# SCH_PROJETO-AFC-_LAYOUT-ATUALIZADO-002__.net
KiCad netlist of a schematic drawn in EasyEDA
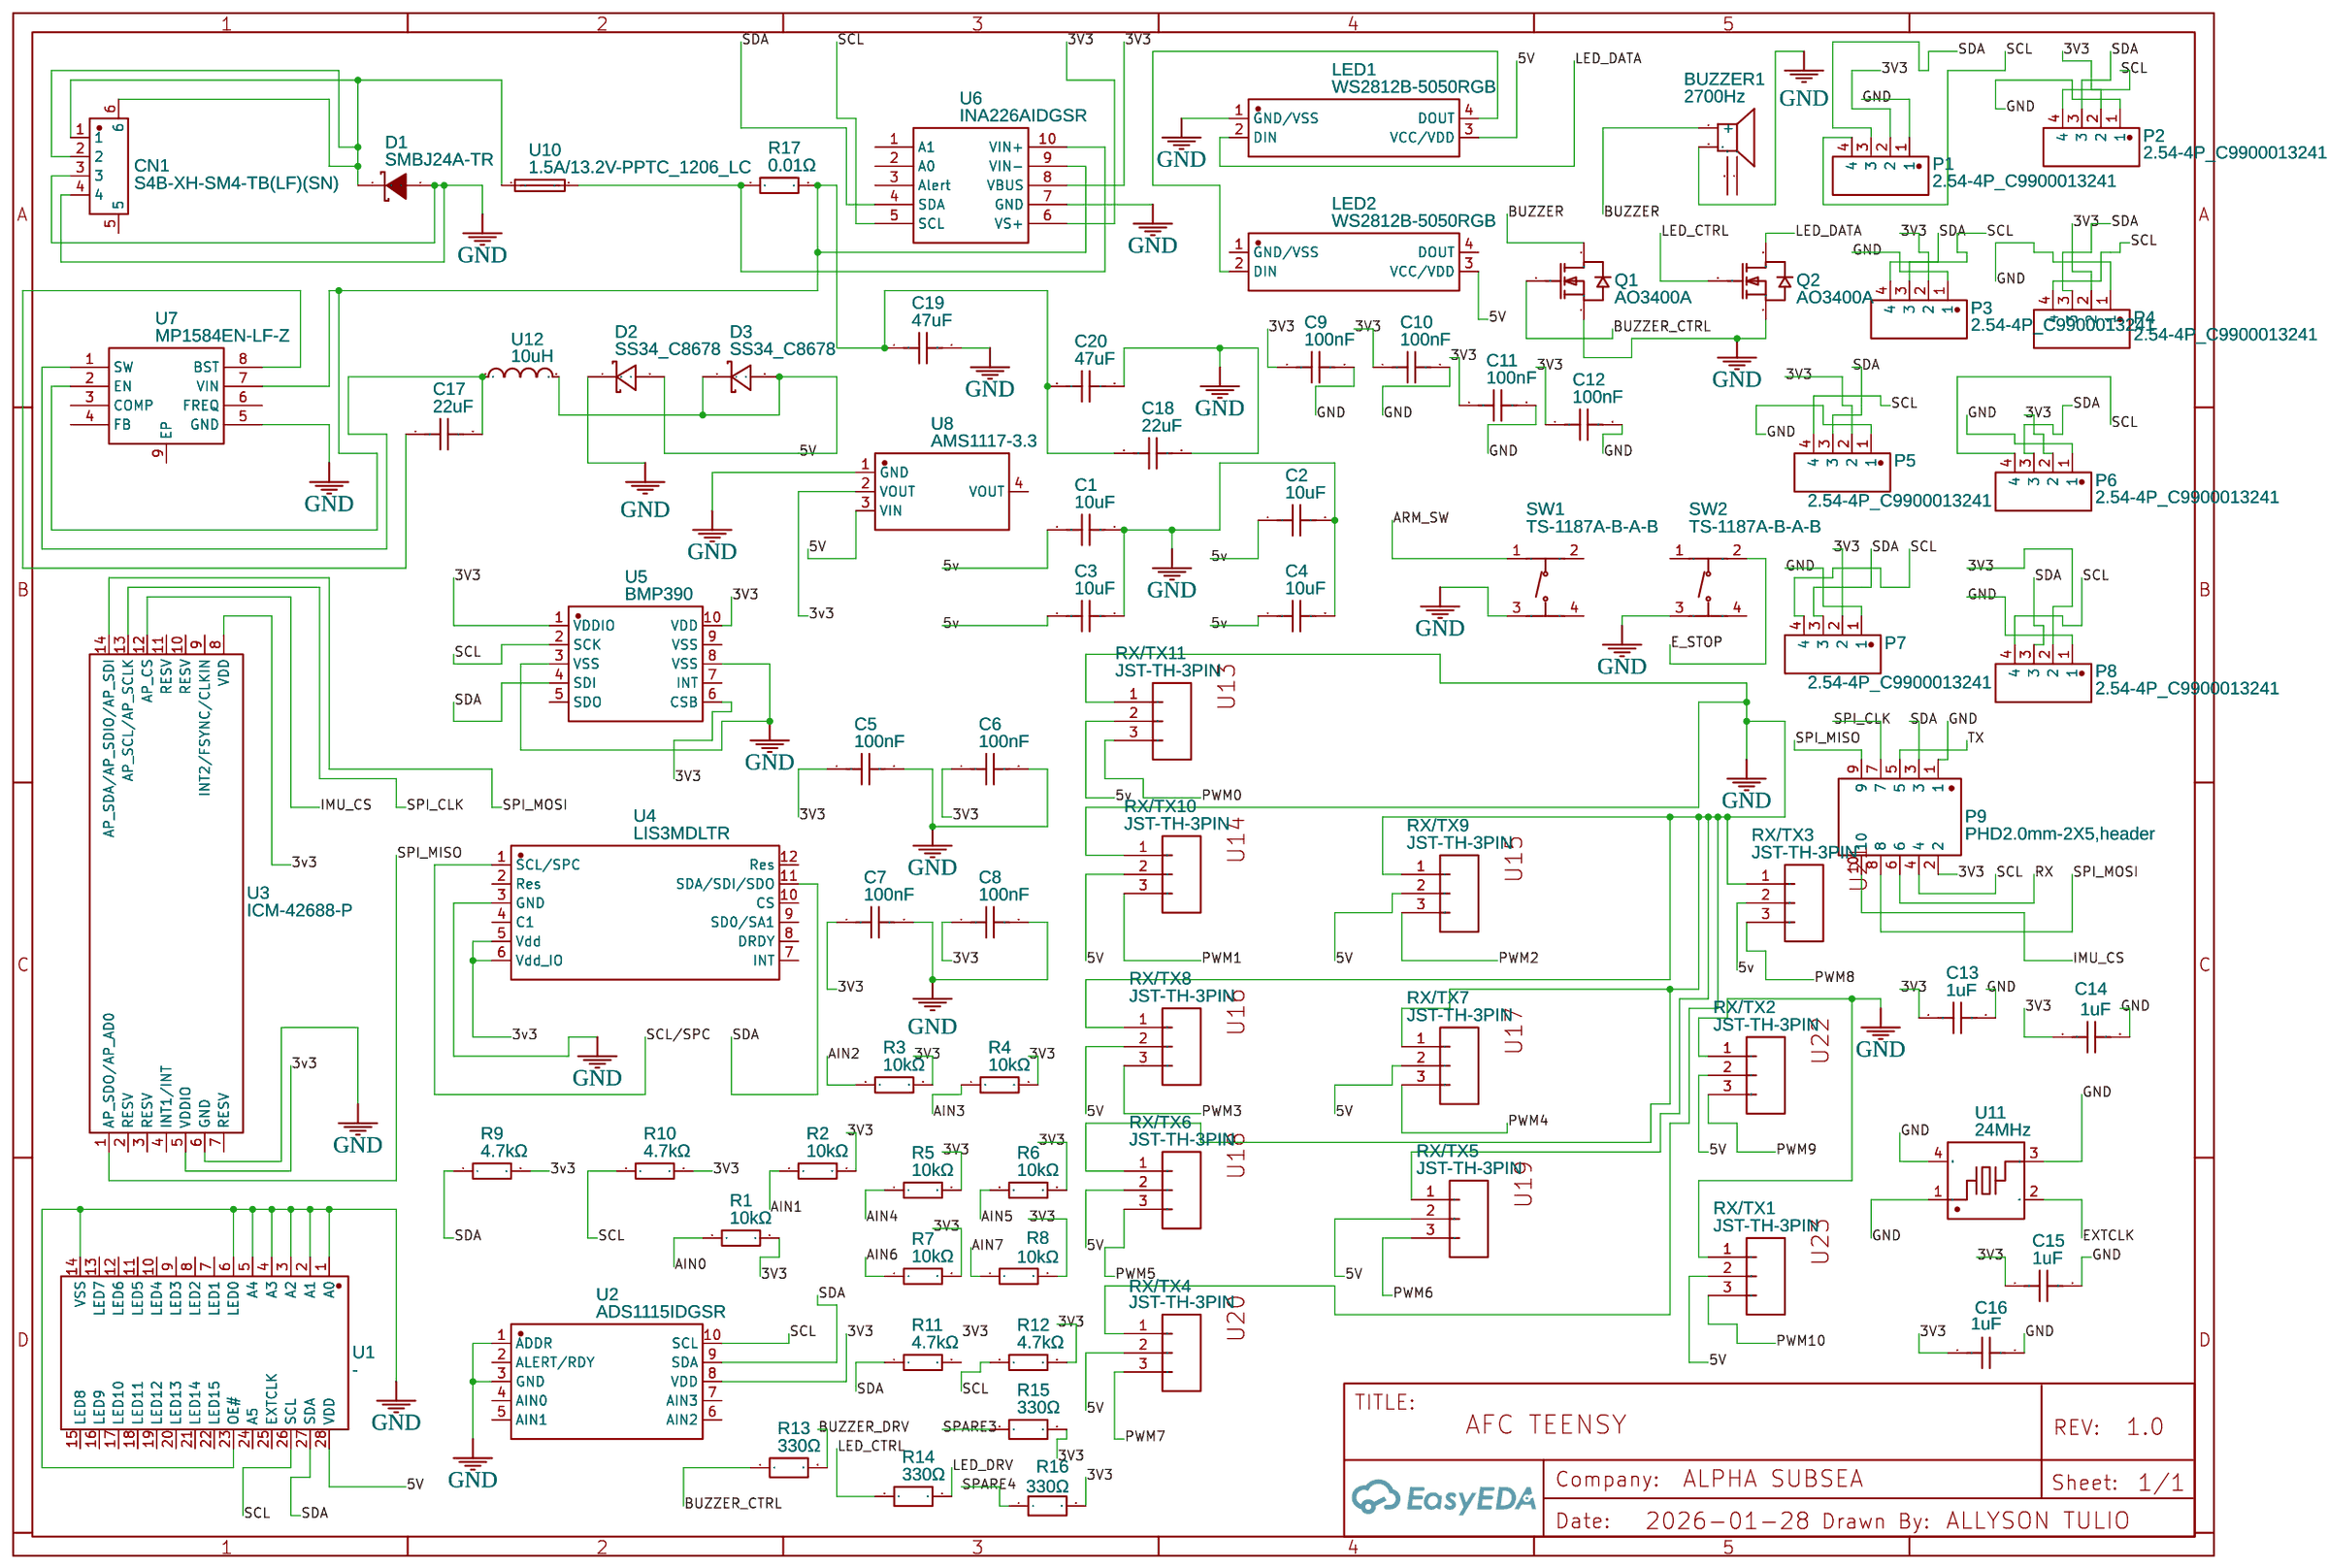
[diagram p0: schematic sheet]

(export (version "E")
  (design (tool "Eeschema 10.0.6"))
  (components
    (comp (ref "BUZZER1")
      (value "2700Hz")
      (fields (field (name "Manufacturer Part") "MLT-8530") (field (name "Manufacturer") "华能"))
      (libsource (lib "") (part "MLT-8530"))
    )
    (comp (ref "C1")
      (value "10uF")
      (fields
        (field (name "Manufacturer Part") "CL21A106KAYNNNE")
        (field (name "Manufacturer") "SAMSUNG(三星)")
      )
      (libsource (lib "") (part "CL21A106KAYNNNE"))
    )
    (comp (ref "C2")
      (value "10uF")
      (fields
        (field (name "Manufacturer Part") "CL21A106KAYNNNE")
        (field (name "Manufacturer") "SAMSUNG(三星)")
      )
      (libsource (lib "") (part "CL21A106KAYNNNE"))
    )
    (comp (ref "C3")
      (value "10uF")
      (fields
        (field (name "Manufacturer Part") "CL21A106KAYNNNE")
        (field (name "Manufacturer") "SAMSUNG(三星)")
      )
      (libsource (lib "") (part "CL21A106KAYNNNE"))
    )
    (comp (ref "C4")
      (value "10uF")
      (fields
        (field (name "Manufacturer Part") "CL21A106KAYNNNE")
        (field (name "Manufacturer") "SAMSUNG(三星)")
      )
      (libsource (lib "") (part "CL21A106KAYNNNE"))
    )
    (comp (ref "C5")
      (value "100nF")
      (fields
        (field (name "Manufacturer Part") "CL05B104KO5NNNC")
        (field (name "Manufacturer") "SAMSUNG(三星)")
      )
      (libsource (lib "") (part "CL05B104KO5NNNC"))
    )
    (comp (ref "C6")
      (value "100nF")
      (fields
        (field (name "Manufacturer Part") "CL05B104KO5NNNC")
        (field (name "Manufacturer") "SAMSUNG(三星)")
      )
      (libsource (lib "") (part "CL05B104KO5NNNC"))
    )
    (comp (ref "C7")
      (value "100nF")
      (fields
        (field (name "Manufacturer Part") "CL05B104KO5NNNC")
        (field (name "Manufacturer") "SAMSUNG(三星)")
      )
      (libsource (lib "") (part "CL05B104KO5NNNC"))
    )
    (comp (ref "C8")
      (value "100nF")
      (fields
        (field (name "Manufacturer Part") "CL05B104KO5NNNC")
        (field (name "Manufacturer") "SAMSUNG(三星)")
      )
      (libsource (lib "") (part "CL05B104KO5NNNC"))
    )
    (comp (ref "C9")
      (value "100nF")
      (fields
        (field (name "Manufacturer Part") "CL05B104KO5NNNC")
        (field (name "Manufacturer") "SAMSUNG(三星)")
      )
      (libsource (lib "") (part "CL05B104KO5NNNC"))
    )
    (comp (ref "C10")
      (value "100nF")
      (fields
        (field (name "Manufacturer Part") "CL05B104KO5NNNC")
        (field (name "Manufacturer") "SAMSUNG(三星)")
      )
      (libsource (lib "") (part "CL05B104KO5NNNC"))
    )
    (comp (ref "C11")
      (value "100nF")
      (fields
        (field (name "Manufacturer Part") "CL05B104KO5NNNC")
        (field (name "Manufacturer") "SAMSUNG(三星)")
      )
      (libsource (lib "") (part "CL05B104KO5NNNC"))
    )
    (comp (ref "C12")
      (value "100nF")
      (fields
        (field (name "Manufacturer Part") "CL05B104KO5NNNC")
        (field (name "Manufacturer") "SAMSUNG(三星)")
      )
      (libsource (lib "") (part "CL05B104KO5NNNC"))
    )
    (comp (ref "C13")
      (value "1uF")
      (fields
        (field (name "Manufacturer Part") "CL05A105KA5NQNC")
        (field (name "Manufacturer") "SAMSUNG(三星)")
      )
      (libsource (lib "") (part "CL05A105KA5NQNC"))
    )
    (comp (ref "C14")
      (value "1uF")
      (fields
        (field (name "Manufacturer Part") "CL05A105KA5NQNC")
        (field (name "Manufacturer") "SAMSUNG(三星)")
      )
      (libsource (lib "") (part "CL05A105KA5NQNC"))
    )
    (comp (ref "C15")
      (value "1uF")
      (fields
        (field (name "Manufacturer Part") "CL05A105KA5NQNC")
        (field (name "Manufacturer") "SAMSUNG(三星)")
      )
      (libsource (lib "") (part "CL05A105KA5NQNC"))
    )
    (comp (ref "C16")
      (value "1uF")
      (fields
        (field (name "Manufacturer Part") "CL05A105KA5NQNC")
        (field (name "Manufacturer") "SAMSUNG(三星)")
      )
      (libsource (lib "") (part "CL05A105KA5NQNC"))
    )
    (comp (ref "C17")
      (value "22uF")
      (fields
        (field (name "Manufacturer Part") "CL21A226MAQNNNE")
        (field (name "Manufacturer") "SAMSUNG(三星)")
      )
      (libsource (lib "") (part "CL21A226MAQNNNE"))
    )
    (comp (ref "C18")
      (value "22uF")
      (fields
        (field (name "Manufacturer Part") "CL21A226MAQNNNE")
        (field (name "Manufacturer") "SAMSUNG(三星)")
      )
      (libsource (lib "") (part "CL21A226MAQNNNE"))
    )
    (comp (ref "C19")
      (value "47uF")
      (fields
        (field (name "Manufacturer Part") "TCC1206X5R476M100HT")
        (field (name "Manufacturer") "CCTC(三环)")
      )
      (libsource (lib "") (part "TCC1206X5R476M100HT"))
    )
    (comp (ref "C20")
      (value "47uF")
      (fields
        (field (name "Manufacturer Part") "TCC1206X5R476M100HT")
        (field (name "Manufacturer") "CCTC(三环)")
      )
      (libsource (lib "") (part "TCC1206X5R476M100HT"))
    )
    (comp (ref "CN1")
      (value "S4B-XH-SM4-TB(LF)(SN)")
      (fields (field (name "Manufacturer") "JST"))
      (libsource (lib "") (part "S4B-XH-SM4-TB(LF)(SN)"))
    )
    (comp (ref "D1")
      (value "SMBJ24A-TR")
      (fields (field (name "Manufacturer") "ST(意法半导体)"))
      (libsource (lib "") (part "SMBJ24A-TR"))
    )
    (comp (ref "D2")
      (value "SS34_C8678")
      (fields (field (name "Manufacturer Part") "SS34") (field (name "Manufacturer") "MDD(辰达半导体)"))
      (libsource (lib "") (part "SS34_C8678"))
    )
    (comp (ref "D3")
      (value "SS34_C8678")
      (fields (field (name "Manufacturer Part") "SS34") (field (name "Manufacturer") "MDD(辰达半导体)"))
      (libsource (lib "") (part "SS34_C8678"))
    )
    (comp (ref "LED1") (value "WS2812B-5050RGB") (libsource (lib "") (part "WS2812B-5050RGB")))
    (comp (ref "LED2") (value "WS2812B-5050RGB") (libsource (lib "") (part "WS2812B-5050RGB")))
    (comp (ref "P1")
      (value "2.54-4P_C9900013241")
      (fields (field (name "Manufacturer Part") "2.54-4P"))
      (libsource (lib "") (part "2.54-4P_C9900013241"))
    )
    (comp (ref "P2")
      (value "2.54-4P_C9900013241")
      (fields (field (name "Manufacturer Part") "2.54-4P"))
      (libsource (lib "") (part "2.54-4P_C9900013241"))
    )
    (comp (ref "P3")
      (value "2.54-4P_C9900013241")
      (fields (field (name "Manufacturer Part") "2.54-4P"))
      (libsource (lib "") (part "2.54-4P_C9900013241"))
    )
    (comp (ref "P4")
      (value "2.54-4P_C9900013241")
      (fields (field (name "Manufacturer Part") "2.54-4P"))
      (libsource (lib "") (part "2.54-4P_C9900013241"))
    )
    (comp (ref "P5")
      (value "2.54-4P_C9900013241")
      (fields (field (name "Manufacturer Part") "2.54-4P"))
      (libsource (lib "") (part "2.54-4P_C9900013241"))
    )
    (comp (ref "P6")
      (value "2.54-4P_C9900013241")
      (fields (field (name "Manufacturer Part") "2.54-4P"))
      (libsource (lib "") (part "2.54-4P_C9900013241"))
    )
    (comp (ref "P7")
      (value "2.54-4P_C9900013241")
      (fields (field (name "Manufacturer Part") "2.54-4P"))
      (libsource (lib "") (part "2.54-4P_C9900013241"))
    )
    (comp (ref "P8")
      (value "2.54-4P_C9900013241")
      (fields (field (name "Manufacturer Part") "2.54-4P"))
      (libsource (lib "") (part "2.54-4P_C9900013241"))
    )
    (comp (ref "P9")
      (value "PHD2.0mm-2X5,header")
      (fields (field (name "Manufacturer Part") "PHD-2X5A") (field (name "Manufacturer") "BOOMELE(博穆精密)"))
      (libsource (lib "") (part "PHD2.0mm-2X5,header"))
    )
    (comp (ref "Q1")
      (value "AO3400A")
      (fields (field (name "Manufacturer") "AOS"))
      (libsource (lib "") (part "AO3400A"))
    )
    (comp (ref "Q2")
      (value "AO3400A")
      (fields (field (name "Manufacturer") "AOS"))
      (libsource (lib "") (part "AO3400A"))
    )
    (comp (ref "R1")
      (value "10kΩ")
      (fields
        (field (name "Manufacturer Part") "0402WGF1002TCE")
        (field (name "Manufacturer") "UNI-ROYAL(厚声)")
      )
      (libsource (lib "") (part "0402WGF1002TCE"))
    )
    (comp (ref "R2")
      (value "10kΩ")
      (fields
        (field (name "Manufacturer Part") "0402WGF1002TCE")
        (field (name "Manufacturer") "UNI-ROYAL(厚声)")
      )
      (libsource (lib "") (part "0402WGF1002TCE"))
    )
    (comp (ref "R3")
      (value "10kΩ")
      (fields
        (field (name "Manufacturer Part") "0402WGF1002TCE")
        (field (name "Manufacturer") "UNI-ROYAL(厚声)")
      )
      (libsource (lib "") (part "0402WGF1002TCE"))
    )
    (comp (ref "R4")
      (value "10kΩ")
      (fields
        (field (name "Manufacturer Part") "0402WGF1002TCE")
        (field (name "Manufacturer") "UNI-ROYAL(厚声)")
      )
      (libsource (lib "") (part "0402WGF1002TCE"))
    )
    (comp (ref "R5")
      (value "10kΩ")
      (fields
        (field (name "Manufacturer Part") "0402WGF1002TCE")
        (field (name "Manufacturer") "UNI-ROYAL(厚声)")
      )
      (libsource (lib "") (part "0402WGF1002TCE"))
    )
    (comp (ref "R6")
      (value "10kΩ")
      (fields
        (field (name "Manufacturer Part") "0402WGF1002TCE")
        (field (name "Manufacturer") "UNI-ROYAL(厚声)")
      )
      (libsource (lib "") (part "0402WGF1002TCE"))
    )
    (comp (ref "R7")
      (value "10kΩ")
      (fields
        (field (name "Manufacturer Part") "0402WGF1002TCE")
        (field (name "Manufacturer") "UNI-ROYAL(厚声)")
      )
      (libsource (lib "") (part "0402WGF1002TCE"))
    )
    (comp (ref "R8")
      (value "10kΩ")
      (fields
        (field (name "Manufacturer Part") "0402WGF1002TCE")
        (field (name "Manufacturer") "UNI-ROYAL(厚声)")
      )
      (libsource (lib "") (part "0402WGF1002TCE"))
    )
    (comp (ref "R9")
      (value "4.7kΩ")
      (fields
        (field (name "Manufacturer Part") "0402WGF4701TCE")
        (field (name "Manufacturer") "UNI-ROYAL(厚声)")
      )
      (libsource (lib "") (part "0402WGF4701TCE"))
    )
    (comp (ref "R10")
      (value "4.7kΩ")
      (fields
        (field (name "Manufacturer Part") "0402WGF4701TCE")
        (field (name "Manufacturer") "UNI-ROYAL(厚声)")
      )
      (libsource (lib "") (part "0402WGF4701TCE"))
    )
    (comp (ref "R11")
      (value "4.7kΩ")
      (fields
        (field (name "Manufacturer Part") "0402WGF4701TCE")
        (field (name "Manufacturer") "UNI-ROYAL(厚声)")
      )
      (libsource (lib "") (part "0402WGF4701TCE"))
    )
    (comp (ref "R12")
      (value "4.7kΩ")
      (fields
        (field (name "Manufacturer Part") "0402WGF4701TCE")
        (field (name "Manufacturer") "UNI-ROYAL(厚声)")
      )
      (libsource (lib "") (part "0402WGF4701TCE"))
    )
    (comp (ref "R13")
      (value "330Ω")
      (fields (field (name "Manufacturer Part") "0402 ±5% 330Ω") (field (name "Manufacturer") "VO(翔胜)"))
      (libsource (lib "") (part "0402 ±5% 330Ω"))
    )
    (comp (ref "R14")
      (value "330Ω")
      (fields (field (name "Manufacturer Part") "0402 ±5% 330Ω") (field (name "Manufacturer") "VO(翔胜)"))
      (libsource (lib "") (part "0402 ±5% 330Ω"))
    )
    (comp (ref "R15")
      (value "330Ω")
      (fields (field (name "Manufacturer Part") "0402 ±5% 330Ω") (field (name "Manufacturer") "VO(翔胜)"))
      (libsource (lib "") (part "0402 ±5% 330Ω"))
    )
    (comp (ref "R16")
      (value "330Ω")
      (fields (field (name "Manufacturer Part") "0402 ±5% 330Ω") (field (name "Manufacturer") "VO(翔胜)"))
      (libsource (lib "") (part "0402 ±5% 330Ω"))
    )
    (comp (ref "R17")
      (value "0.01Ω")
      (fields (field (name "Manufacturer Part") "MRF6432(2512)LR010JTS") (field (name "Manufacturer") "SUP"))
      (libsource (lib "") (part "MRF6432(2512)LR010JTS"))
    )
    (comp (ref "RX/TX1")
      (value "JST-TH-3PIN")
      (fields (field (name "Manufacturer Part") "JST-XH 3P"))
      (libsource (lib "") (part "JST XH 3P 2.54 PITCH_1"))
    )
    (comp (ref "RX/TX2")
      (value "JST-TH-3PIN")
      (fields (field (name "Manufacturer Part") "JST-XH 3P"))
      (libsource (lib "") (part "JST XH 3P 2.54 PITCH_4"))
    )
    (comp (ref "RX/TX3")
      (value "JST-TH-3PIN")
      (fields (field (name "Manufacturer Part") "JST-XH 3P"))
      (libsource (lib "") (part "JST XH 3P 2.54 PITCH_5"))
    )
    (comp (ref "RX/TX4")
      (value "JST-TH-3PIN")
      (fields (field (name "Manufacturer Part") "JST-XH 3P"))
      (libsource (lib "") (part "JST XH 3P 2.54 PITCH"))
    )
    (comp (ref "RX/TX5")
      (value "JST-TH-3PIN")
      (fields (field (name "Manufacturer Part") "JST-XH 3P"))
      (libsource (lib "") (part "JST XH 3P 2.54 PITCH_2"))
    )
    (comp (ref "RX/TX6")
      (value "JST-TH-3PIN")
      (fields (field (name "Manufacturer Part") "JST-XH 3P"))
      (libsource (lib "") (part "JST XH 3P 2.54 PITCH_9"))
    )
    (comp (ref "RX/TX7")
      (value "JST-TH-3PIN")
      (fields (field (name "Manufacturer Part") "JST-XH 3P"))
      (libsource (lib "") (part "JST XH 3P 2.54 PITCH_10"))
    )
    (comp (ref "RX/TX8")
      (value "JST-TH-3PIN")
      (fields (field (name "Manufacturer Part") "JST-XH 3P"))
      (libsource (lib "") (part "JST XH 3P 2.54 PITCH_7"))
    )
    (comp (ref "RX/TX9")
      (value "JST-TH-3PIN")
      (fields (field (name "Manufacturer Part") "JST-XH 3P"))
      (libsource (lib "") (part "JST XH 3P 2.54 PITCH_3"))
    )
    (comp (ref "RX/TX10")
      (value "JST-TH-3PIN")
      (fields (field (name "Manufacturer Part") "JST-XH 3P"))
      (libsource (lib "") (part "JST XH 3P 2.54 PITCH_8"))
    )
    (comp (ref "RX/TX11")
      (value "JST-TH-3PIN")
      (fields (field (name "Manufacturer Part") "JST-XH 3P"))
      (libsource (lib "") (part "JST XH 3P 2.54 PITCH_6"))
    )
    (comp (ref "SW1")
      (value "TS-1187A-B-A-B")
      (fields (field (name "Manufacturer") "XKB Connection(中国星坤)"))
      (libsource (lib "") (part "TS-1187A-B-A-B"))
    )
    (comp (ref "SW2")
      (value "TS-1187A-B-A-B")
      (fields (field (name "Manufacturer") "XKB Connection(中国星坤)"))
      (libsource (lib "") (part "TS-1187A-B-A-B"))
    )
    (comp (ref "U1")
      (value "-")
      (fields (field (name "Manufacturer Part") "PCA9685PW,118") (field (name "Manufacturer") "NXP(恩智浦)"))
      (libsource (lib "") (part "PCA9685PW,118"))
    )
    (comp (ref "U2")
      (value "ADS1115IDGSR")
      (fields (field (name "Manufacturer") "TI(德州仪器)"))
      (libsource (lib "") (part "ADS1115IDGSR"))
    )
    (comp (ref "U3")
      (value "ICM-42688-P")
      (fields (field (name "Manufacturer") "TDK InvenSense(应美盛)"))
      (libsource (lib "") (part "ICM-42688-P"))
    )
    (comp (ref "U4")
      (value "LIS3MDLTR")
      (fields (field (name "Manufacturer") "ST(意法半导体)"))
      (libsource (lib "") (part "LIS3MDLTR"))
    )
    (comp (ref "U5") (value "BMP390") (libsource (lib "") (part "BMP390")))
    (comp (ref "U6")
      (value "INA226AIDGSR")
      (fields (field (name "Manufacturer") "TI(德州仪器)"))
      (libsource (lib "") (part "INA226AIDGSR"))
    )
    (comp (ref "U7")
      (value "MP1584EN-LF-Z")
      (fields (field (name "Manufacturer") "MPS(芯源)"))
      (libsource (lib "") (part "MP1584EN-LF-Z"))
    )
    (comp (ref "U8")
      (value "AMS1117-3.3")
      (fields (field (name "Manufacturer") "AMS"))
      (libsource (lib "") (part "AMS1117-3.3"))
    )
    (comp (ref "U10") (value "1.5A/13.2V-PPTC_1206_LC") (libsource (lib "") (part "1.5A/13.2V-PPTC_1206_LC")))
    (comp (ref "U11")
      (value "24MHz")
      (fields (field (name "Manufacturer Part") "7325-2400A1210-03") (field (name "Manufacturer") "XTY(新天源)"))
      (libsource (lib "") (part "7325-2400A1210-03"))
    )
    (comp (ref "U12")
      (value "10uH")
      (fields
        (field (name "Manufacturer Part") "MWSA0503S-100MT")
        (field (name "Manufacturer") "Sunlord(顺络)")
      )
      (libsource (lib "") (part "MWSA0503S-100MT"))
    )
  )
  (nets
    (net (code "1") (name "/3V3") (class "Default")
      (node (ref "C10") (pin "1") (pinfunction "1_1") (pintype "unspecified"))
      (node (ref "C11") (pin "1") (pinfunction "1_1") (pintype "unspecified"))
      (node (ref "C12") (pin "1") (pinfunction "1_1") (pintype "unspecified"))
      (node (ref "C13") (pin "1") (pinfunction "1_1") (pintype "unspecified"))
      (node (ref "C14") (pin "1") (pinfunction "1_1") (pintype "unspecified"))
      (node (ref "C15") (pin "1") (pinfunction "1_1") (pintype "unspecified"))
      (node (ref "C16") (pin "1") (pinfunction "1_1") (pintype "unspecified"))
      (node (ref "C5") (pin "1") (pinfunction "1_1") (pintype "unspecified"))
      (node (ref "C6") (pin "1") (pinfunction "1_1") (pintype "unspecified"))
      (node (ref "C7") (pin "1") (pinfunction "1_1") (pintype "unspecified"))
      (node (ref "C8") (pin "1") (pinfunction "1_1") (pintype "unspecified"))
      (node (ref "C9") (pin "1") (pinfunction "1_1") (pintype "unspecified"))
      (node (ref "P1") (pin "2") (pinfunction "2_2") (pintype "unspecified"))
      (node (ref "P2") (pin "2") (pinfunction "2_2") (pintype "unspecified"))
      (node (ref "P3") (pin "2") (pinfunction "2_2") (pintype "unspecified"))
      (node (ref "P4") (pin "2") (pinfunction "2_2") (pintype "unspecified"))
      (node (ref "P5") (pin "2") (pinfunction "2_2") (pintype "unspecified"))
      (node (ref "P6") (pin "2") (pinfunction "2_2") (pintype "unspecified"))
      (node (ref "P7") (pin "2") (pinfunction "2_2") (pintype "unspecified"))
      (node (ref "P8") (pin "2") (pinfunction "2_2") (pintype "unspecified"))
      (node (ref "P9") (pin "2") (pinfunction "2_2") (pintype "unspecified"))
      (node (ref "R1") (pin "2") (pinfunction "2_2") (pintype "input"))
      (node (ref "R10") (pin "2") (pinfunction "2_2") (pintype "input"))
      (node (ref "R12") (pin "2") (pinfunction "2_2") (pintype "input"))
      (node (ref "R15") (pin "2") (pinfunction "2_2") (pintype "unspecified"))
      (node (ref "R16") (pin "2") (pinfunction "2_2") (pintype "unspecified"))
      (node (ref "R2") (pin "2") (pinfunction "2_2") (pintype "input"))
      (node (ref "R3") (pin "2") (pinfunction "2_2") (pintype "input"))
      (node (ref "R4") (pin "2") (pinfunction "2_2") (pintype "input"))
      (node (ref "R5") (pin "2") (pinfunction "2_2") (pintype "input"))
      (node (ref "R6") (pin "2") (pinfunction "2_2") (pintype "input"))
      (node (ref "R7") (pin "2") (pinfunction "2_2") (pintype "input"))
      (node (ref "R8") (pin "2") (pinfunction "2_2") (pintype "input"))
      (node (ref "U2") (pin "8") (pinfunction "VDD_8") (pintype "unspecified"))
      (node (ref "U5") (pin "1") (pinfunction "VDDIO_1") (pintype "unspecified"))
      (node (ref "U5") (pin "10") (pinfunction "VDD_10") (pintype "unspecified"))
      (node (ref "U5") (pin "6") (pinfunction "CSB_6") (pintype "unspecified"))
      (node (ref "U6") (pin "6") (pinfunction "VS+_6") (pintype "unspecified"))
      (node (ref "U6") (pin "8") (pinfunction "VBUS_8") (pintype "unspecified"))
    )
    (net (code "2") (name "/3v3") (class "Default")
      (node (ref "R9") (pin "2") (pinfunction "2_2") (pintype "input"))
      (node (ref "U3") (pin "5") (pinfunction "VDDIO_5") (pintype "unspecified"))
      (node (ref "U3") (pin "8") (pinfunction "VDD_8") (pintype "unspecified"))
      (node (ref "U4") (pin "5") (pinfunction "Vdd_5") (pintype "unspecified"))
      (node (ref "U4") (pin "6") (pinfunction "Vdd_IO_6") (pintype "unspecified"))
      (node (ref "U8") (pin "2") (pinfunction "VOUT_2") (pintype "unspecified"))
    )
    (net (code "3") (name "/5V") (class "Default")
      (node (ref "D2") (pin "2") (pinfunction "A_2") (pintype "unspecified"))
      (node (ref "D3") (pin "1") (pinfunction "K_1") (pintype "unspecified"))
      (node (ref "D3") (pin "2") (pinfunction "A_2") (pintype "unspecified"))
      (node (ref "LED1") (pin "3") (pinfunction "VCC/VDD_3") (pintype "unspecified"))
      (node (ref "LED2") (pin "3") (pinfunction "VCC/VDD_3") (pintype "unspecified"))
      (node (ref "RX/TX1") (pin "2") (pinfunction "2_2") (pintype "unspecified"))
      (node (ref "RX/TX10") (pin "2") (pinfunction "2_2") (pintype "unspecified"))
      (node (ref "RX/TX2") (pin "2") (pinfunction "2_2") (pintype "unspecified"))
      (node (ref "RX/TX4") (pin "2") (pinfunction "2_2") (pintype "unspecified"))
      (node (ref "RX/TX5") (pin "2") (pinfunction "2_2") (pintype "unspecified"))
      (node (ref "RX/TX6") (pin "2") (pinfunction "2_2") (pintype "unspecified"))
      (node (ref "RX/TX7") (pin "2") (pinfunction "2_2") (pintype "unspecified"))
      (node (ref "RX/TX8") (pin "2") (pinfunction "2_2") (pintype "unspecified"))
      (node (ref "RX/TX9") (pin "2") (pinfunction "2_2") (pintype "unspecified"))
      (node (ref "U1") (pin "28") (pinfunction "VDD_28") (pintype "unspecified"))
      (node (ref "U12") (pin "2") (pinfunction "2_2") (pintype "unspecified"))
      (node (ref "U8") (pin "3") (pinfunction "VIN_3") (pintype "unspecified"))
    )
    (net (code "4") (name "/5v") (class "Default")
      (node (ref "C1") (pin "1") (pinfunction "1_1") (pintype "unspecified"))
      (node (ref "C2") (pin "1") (pinfunction "1_1") (pintype "unspecified"))
      (node (ref "C3") (pin "1") (pinfunction "1_1") (pintype "unspecified"))
      (node (ref "C4") (pin "1") (pinfunction "1_1") (pintype "unspecified"))
      (node (ref "RX/TX11") (pin "2") (pinfunction "2_2") (pintype "unspecified"))
      (node (ref "RX/TX3") (pin "2") (pinfunction "2_2") (pintype "unspecified"))
    )
    (net (code "5") (name "/AIN0") (class "Default")
      (node (ref "R1") (pin "1") (pinfunction "1_1") (pintype "input"))
    )
    (net (code "6") (name "/AIN1") (class "Default")
      (node (ref "R2") (pin "1") (pinfunction "1_1") (pintype "input"))
    )
    (net (code "7") (name "/AIN2") (class "Default")
      (node (ref "R3") (pin "1") (pinfunction "1_1") (pintype "input"))
    )
    (net (code "8") (name "/AIN3") (class "Default")
      (node (ref "R4") (pin "1") (pinfunction "1_1") (pintype "input"))
    )
    (net (code "9") (name "/AIN4") (class "Default")
      (node (ref "R5") (pin "1") (pinfunction "1_1") (pintype "input"))
    )
    (net (code "10") (name "/AIN5") (class "Default")
      (node (ref "R6") (pin "1") (pinfunction "1_1") (pintype "input"))
    )
    (net (code "11") (name "/AIN6") (class "Default")
      (node (ref "R7") (pin "1") (pinfunction "1_1") (pintype "input"))
    )
    (net (code "12") (name "/AIN7") (class "Default")
      (node (ref "R8") (pin "1") (pinfunction "1_1") (pintype "input"))
    )
    (net (code "13") (name "/ARM_SW") (class "Default")
      (node (ref "SW1") (pin "1") (pinfunction "A_1") (pintype "unspecified"))
    )
    (net (code "14") (name "/BUZZER") (class "Default")
      (node (ref "BUZZER1") (pin "1") (pinfunction "+_1") (pintype "unspecified"))
      (node (ref "Q1") (pin "3") (pinfunction "D_3") (pintype "unspecified"))
    )
    (net (code "15") (name "/BUZZER_CTRL") (class "Default")
      (node (ref "Q1") (pin "1") (pinfunction "G_1") (pintype "unspecified"))
      (node (ref "R13") (pin "1") (pinfunction "1_1") (pintype "unspecified"))
    )
    (net (code "16") (name "/BUZZER_DRV") (class "Default")
      (node (ref "R13") (pin "2") (pinfunction "2_2") (pintype "unspecified"))
    )
    (net (code "17") (name "/EXTCLK") (class "Default")
      (node (ref "U11") (pin "2") (pinfunction "GND_2") (pintype "input"))
    )
    (net (code "18") (name "/E_STOP") (class "Default")
      (node (ref "SW2") (pin "2") (pinfunction "B_2") (pintype "unspecified"))
    )
    (net (code "19") (name "/IMU_CS") (class "Default")
      (node (ref "P9") (pin "10") (pinfunction "10_10") (pintype "unspecified"))
      (node (ref "U3") (pin "12") (pinfunction "AP_CS_12") (pintype "unspecified"))
    )
    (net (code "20") (name "/LED_CTRL") (class "Default")
      (node (ref "Q2") (pin "1") (pinfunction "G_1") (pintype "unspecified"))
      (node (ref "R14") (pin "1") (pinfunction "1_1") (pintype "unspecified"))
    )
    (net (code "21") (name "/LED_DATA") (class "Default")
      (node (ref "LED1") (pin "2") (pinfunction "DIN_2") (pintype "unspecified"))
      (node (ref "Q2") (pin "3") (pinfunction "D_3") (pintype "unspecified"))
    )
    (net (code "22") (name "/LED_DRV") (class "Default")
      (node (ref "R14") (pin "2") (pinfunction "2_2") (pintype "unspecified"))
    )
    (net (code "23") (name "/PWM0") (class "Default")
      (node (ref "RX/TX11") (pin "3") (pinfunction "3_3") (pintype "unspecified"))
    )
    (net (code "24") (name "/PWM1") (class "Default")
      (node (ref "RX/TX10") (pin "3") (pinfunction "3_3") (pintype "unspecified"))
    )
    (net (code "25") (name "/PWM2") (class "Default")
      (node (ref "RX/TX9") (pin "3") (pinfunction "3_3") (pintype "unspecified"))
    )
    (net (code "26") (name "/PWM3") (class "Default")
      (node (ref "RX/TX8") (pin "3") (pinfunction "3_3") (pintype "unspecified"))
    )
    (net (code "27") (name "/PWM4") (class "Default")
      (node (ref "RX/TX7") (pin "3") (pinfunction "3_3") (pintype "unspecified"))
    )
    (net (code "28") (name "/PWM5") (class "Default")
      (node (ref "RX/TX6") (pin "3") (pinfunction "3_3") (pintype "unspecified"))
    )
    (net (code "29") (name "/PWM6") (class "Default")
      (node (ref "RX/TX5") (pin "3") (pinfunction "3_3") (pintype "unspecified"))
    )
    (net (code "30") (name "/PWM7") (class "Default")
      (node (ref "RX/TX4") (pin "3") (pinfunction "3_3") (pintype "unspecified"))
    )
    (net (code "31") (name "/PWM8") (class "Default")
      (node (ref "RX/TX3") (pin "3") (pinfunction "3_3") (pintype "unspecified"))
    )
    (net (code "32") (name "/PWM9") (class "Default")
      (node (ref "RX/TX2") (pin "3") (pinfunction "3_3") (pintype "unspecified"))
    )
    (net (code "33") (name "/PWM10") (class "Default")
      (node (ref "RX/TX1") (pin "3") (pinfunction "3_3") (pintype "unspecified"))
    )
    (net (code "34") (name "/RX") (class "Default")
      (node (ref "P9") (pin "6") (pinfunction "6_6") (pintype "unspecified"))
    )
    (net (code "35") (name "/SCL") (class "Default")
      (node (ref "P1") (pin "4") (pinfunction "4_4") (pintype "unspecified"))
      (node (ref "P2") (pin "4") (pinfunction "4_4") (pintype "unspecified"))
      (node (ref "P3") (pin "4") (pinfunction "4_4") (pintype "unspecified"))
      (node (ref "P4") (pin "4") (pinfunction "4_4") (pintype "unspecified"))
      (node (ref "P5") (pin "4") (pinfunction "4_4") (pintype "unspecified"))
      (node (ref "P6") (pin "4") (pinfunction "4_4") (pintype "unspecified"))
      (node (ref "P7") (pin "4") (pinfunction "4_4") (pintype "unspecified"))
      (node (ref "P8") (pin "4") (pinfunction "4_4") (pintype "unspecified"))
      (node (ref "P9") (pin "4") (pinfunction "4_4") (pintype "unspecified"))
      (node (ref "R10") (pin "1") (pinfunction "1_1") (pintype "input"))
      (node (ref "R12") (pin "1") (pinfunction "1_1") (pintype "input"))
      (node (ref "U1") (pin "26") (pinfunction "SCL_26") (pintype "unspecified"))
      (node (ref "U2") (pin "10") (pinfunction "SCL_10") (pintype "unspecified"))
      (node (ref "U5") (pin "2") (pinfunction "SCK_2") (pintype "unspecified"))
      (node (ref "U6") (pin "5") (pinfunction "SCL_5") (pintype "unspecified"))
    )
    (net (code "36") (name "/SCL{slash}SPC") (class "Default")
      (node (ref "U4") (pin "1") (pinfunction "SCL/SPC_1") (pintype "unspecified"))
    )
    (net (code "37") (name "/SDA") (class "Default")
      (node (ref "P1") (pin "3") (pinfunction "3_3") (pintype "unspecified"))
      (node (ref "P2") (pin "3") (pinfunction "3_3") (pintype "unspecified"))
      (node (ref "P3") (pin "3") (pinfunction "3_3") (pintype "unspecified"))
      (node (ref "P4") (pin "3") (pinfunction "3_3") (pintype "unspecified"))
      (node (ref "P5") (pin "3") (pinfunction "3_3") (pintype "unspecified"))
      (node (ref "P6") (pin "3") (pinfunction "3_3") (pintype "unspecified"))
      (node (ref "P7") (pin "3") (pinfunction "3_3") (pintype "unspecified"))
      (node (ref "P8") (pin "3") (pinfunction "3_3") (pintype "unspecified"))
      (node (ref "P9") (pin "3") (pinfunction "3_3") (pintype "unspecified"))
      (node (ref "R11") (pin "1") (pinfunction "1_1") (pintype "input"))
      (node (ref "R9") (pin "1") (pinfunction "1_1") (pintype "input"))
      (node (ref "U1") (pin "27") (pinfunction "SDA_27") (pintype "unspecified"))
      (node (ref "U2") (pin "9") (pinfunction "SDA_9") (pintype "unspecified"))
      (node (ref "U4") (pin "11") (pinfunction "SDA/SDI/SDO_11") (pintype "unspecified"))
      (node (ref "U5") (pin "4") (pinfunction "SDI_4") (pintype "unspecified"))
      (node (ref "U6") (pin "4") (pinfunction "SDA_4") (pintype "unspecified"))
    )
    (net (code "38") (name "/SPARE3") (class "Default")
      (node (ref "R15") (pin "1") (pinfunction "1_1") (pintype "unspecified"))
    )
    (net (code "39") (name "/SPARE4") (class "Default")
      (node (ref "R16") (pin "1") (pinfunction "1_1") (pintype "unspecified"))
    )
    (net (code "40") (name "/SPI_CLK") (class "Default")
      (node (ref "P9") (pin "7") (pinfunction "7_7") (pintype "unspecified"))
      (node (ref "U3") (pin "13") (pinfunction "AP_SCL/AP_SCLK_13") (pintype "unspecified"))
    )
    (net (code "41") (name "/SPI_MISO") (class "Default")
      (node (ref "P9") (pin "9") (pinfunction "9_9") (pintype "unspecified"))
      (node (ref "U3") (pin "1") (pinfunction "AP_SDO/AP_AD0_1") (pintype "unspecified"))
    )
    (net (code "42") (name "/SPI_MOSI") (class "Default")
      (node (ref "P9") (pin "8") (pinfunction "8_8") (pintype "unspecified"))
      (node (ref "U3") (pin "14") (pinfunction "AP_SDA/AP_SDIO/AP_SDI_14") (pintype "unspecified"))
    )
    (net (code "43") (name "/TX") (class "Default")
      (node (ref "P9") (pin "5") (pinfunction "5_5") (pintype "unspecified"))
    )
    (net (code "44") (name "GND") (class "Default")
      (node (ref "BUZZER1") (pin "2") (pinfunction "2_2") (pintype "unspecified"))
      (node (ref "C1") (pin "2") (pinfunction "2_2") (pintype "unspecified"))
      (node (ref "C10") (pin "2") (pinfunction "2_2") (pintype "unspecified"))
      (node (ref "C11") (pin "2") (pinfunction "2_2") (pintype "unspecified"))
      (node (ref "C12") (pin "2") (pinfunction "2_2") (pintype "unspecified"))
      (node (ref "C13") (pin "2") (pinfunction "2_2") (pintype "unspecified"))
      (node (ref "C14") (pin "2") (pinfunction "2_2") (pintype "unspecified"))
      (node (ref "C15") (pin "2") (pinfunction "2_2") (pintype "unspecified"))
      (node (ref "C16") (pin "2") (pinfunction "2_2") (pintype "unspecified"))
      (node (ref "C18") (pin "2") (pinfunction "2_2") (pintype "unspecified"))
      (node (ref "C19") (pin "2") (pinfunction "2_2") (pintype "unspecified"))
      (node (ref "C2") (pin "2") (pinfunction "2_2") (pintype "unspecified"))
      (node (ref "C20") (pin "2") (pinfunction "2_2") (pintype "unspecified"))
      (node (ref "C3") (pin "2") (pinfunction "2_2") (pintype "unspecified"))
      (node (ref "C4") (pin "2") (pinfunction "2_2") (pintype "unspecified"))
      (node (ref "C5") (pin "2") (pinfunction "2_2") (pintype "unspecified"))
      (node (ref "C6") (pin "2") (pinfunction "2_2") (pintype "unspecified"))
      (node (ref "C7") (pin "2") (pinfunction "2_2") (pintype "unspecified"))
      (node (ref "C8") (pin "2") (pinfunction "2_2") (pintype "unspecified"))
      (node (ref "C9") (pin "2") (pinfunction "2_2") (pintype "unspecified"))
      (node (ref "CN1") (pin "3") (pinfunction "3_3") (pintype "unspecified"))
      (node (ref "CN1") (pin "4") (pinfunction "4_4") (pintype "unspecified"))
      (node (ref "D1") (pin "2") (pinfunction "A_2") (pintype "unspecified"))
      (node (ref "D2") (pin "1") (pinfunction "K_1") (pintype "unspecified"))
      (node (ref "LED1") (pin "1") (pinfunction "GND/VSS_1") (pintype "unspecified"))
      (node (ref "P1") (pin "1") (pinfunction "1_1") (pintype "unspecified"))
      (node (ref "P2") (pin "1") (pinfunction "1_1") (pintype "unspecified"))
      (node (ref "P3") (pin "1") (pinfunction "1_1") (pintype "unspecified"))
      (node (ref "P4") (pin "1") (pinfunction "1_1") (pintype "unspecified"))
      (node (ref "P5") (pin "1") (pinfunction "1_1") (pintype "unspecified"))
      (node (ref "P6") (pin "1") (pinfunction "1_1") (pintype "unspecified"))
      (node (ref "P7") (pin "1") (pinfunction "1_1") (pintype "unspecified"))
      (node (ref "P8") (pin "1") (pinfunction "1_1") (pintype "unspecified"))
      (node (ref "P9") (pin "1") (pinfunction "1_1") (pintype "unspecified"))
      (node (ref "Q1") (pin "2") (pinfunction "S_2") (pintype "unspecified"))
      (node (ref "Q2") (pin "2") (pinfunction "S_2") (pintype "unspecified"))
      (node (ref "RX/TX1") (pin "1") (pinfunction "1_1") (pintype "unspecified"))
      (node (ref "RX/TX10") (pin "1") (pinfunction "1_1") (pintype "unspecified"))
      (node (ref "RX/TX11") (pin "1") (pinfunction "1_1") (pintype "unspecified"))
      (node (ref "RX/TX2") (pin "1") (pinfunction "1_1") (pintype "unspecified"))
      (node (ref "RX/TX3") (pin "1") (pinfunction "1_1") (pintype "unspecified"))
      (node (ref "RX/TX4") (pin "1") (pinfunction "1_1") (pintype "unspecified"))
      (node (ref "RX/TX5") (pin "1") (pinfunction "1_1") (pintype "unspecified"))
      (node (ref "RX/TX6") (pin "1") (pinfunction "1_1") (pintype "unspecified"))
      (node (ref "RX/TX7") (pin "1") (pinfunction "1_1") (pintype "unspecified"))
      (node (ref "RX/TX8") (pin "1") (pinfunction "1_1") (pintype "unspecified"))
      (node (ref "RX/TX9") (pin "1") (pinfunction "1_1") (pintype "unspecified"))
      (node (ref "SW1") (pin "3") (pinfunction "C_3") (pintype "unspecified"))
      (node (ref "SW2") (pin "3") (pinfunction "C_3") (pintype "unspecified"))
      (node (ref "U1") (pin "1") (pinfunction "A0_1") (pintype "unspecified"))
      (node (ref "U1") (pin "14") (pinfunction "VSS_14") (pintype "unspecified"))
      (node (ref "U1") (pin "2") (pinfunction "A1_2") (pintype "unspecified"))
      (node (ref "U1") (pin "23") (pinfunction "OE#_23") (pintype "unspecified"))
      (node (ref "U1") (pin "3") (pinfunction "A2_3") (pintype "unspecified"))
      (node (ref "U1") (pin "4") (pinfunction "A3_4") (pintype "unspecified"))
      (node (ref "U1") (pin "5") (pinfunction "A4_5") (pintype "unspecified"))
      (node (ref "U1") (pin "6") (pinfunction "LED0_6") (pintype "unspecified"))
      (node (ref "U11") (pin "1") (pinfunction "1_1") (pintype "input"))
      (node (ref "U11") (pin "3") (pinfunction "3_3") (pintype "input"))
      (node (ref "U11") (pin "4") (pinfunction "GND_4") (pintype "input"))
      (node (ref "U2") (pin "1") (pinfunction "ADDR_1") (pintype "unspecified"))
      (node (ref "U2") (pin "3") (pinfunction "GND_3") (pintype "unspecified"))
      (node (ref "U3") (pin "6") (pinfunction "GND_6") (pintype "unspecified"))
      (node (ref "U4") (pin "3") (pinfunction "GND_3") (pintype "unspecified"))
      (node (ref "U5") (pin "3") (pinfunction "VSS_3") (pintype "unspecified"))
      (node (ref "U5") (pin "8") (pinfunction "VSS_8") (pintype "unspecified"))
      (node (ref "U6") (pin "7") (pinfunction "GND_7") (pintype "unspecified"))
      (node (ref "U7") (pin "5") (pinfunction "GND_5") (pintype "unspecified"))
      (node (ref "U8") (pin "1") (pinfunction "GND_1") (pintype "unspecified"))
    )
    (net (code "45") (name "Net-(D1-K)") (class "Default")
      (node (ref "CN1") (pin "1") (pinfunction "1_1") (pintype "unspecified"))
      (node (ref "CN1") (pin "2") (pinfunction "2_2") (pintype "unspecified"))
      (node (ref "CN1") (pin "6") (pinfunction "6_6") (pintype "unspecified"))
      (node (ref "D1") (pin "1") (pinfunction "K_1") (pintype "unspecified"))
      (node (ref "U10") (pin "1") (pinfunction "1_1") (pintype "unspecified"))
    )
    (net (code "46") (name "Net-(LED1-DOUT)") (class "Default")
      (node (ref "LED1") (pin "4") (pinfunction "DOUT_4") (pintype "unspecified"))
      (node (ref "LED2") (pin "2") (pinfunction "DIN_2") (pintype "unspecified"))
    )
    (net (code "47") (name "Net-(U6-VIN+)") (class "Default")
      (node (ref "R17") (pin "1") (pinfunction "1_1") (pintype "input"))
      (node (ref "U10") (pin "2") (pinfunction "2_2") (pintype "unspecified"))
      (node (ref "U6") (pin "10") (pinfunction "VIN+_10") (pintype "unspecified"))
    )
    (net (code "48") (name "Net-(U6-VIN-)") (class "Default")
      (node (ref "C18") (pin "1") (pinfunction "1_1") (pintype "unspecified"))
      (node (ref "C19") (pin "1") (pinfunction "1_1") (pintype "unspecified"))
      (node (ref "C20") (pin "1") (pinfunction "1_1") (pintype "unspecified"))
      (node (ref "R17") (pin "2") (pinfunction "2_2") (pintype "input"))
      (node (ref "U6") (pin "9") (pinfunction "VIN-_9") (pintype "unspecified"))
      (node (ref "U7") (pin "2") (pinfunction "EN_2") (pintype "unspecified"))
      (node (ref "U7") (pin "7") (pinfunction "VIN_7") (pintype "unspecified"))
    )
    (net (code "49") (name "Net-(U7-BST)") (class "Default")
      (node (ref "C17") (pin "1") (pinfunction "1_1") (pintype "unspecified"))
      (node (ref "U7") (pin "8") (pinfunction "BST_8") (pintype "unspecified"))
    )
    (net (code "50") (name "Net-(U7-SW)") (class "Default")
      (node (ref "C17") (pin "2") (pinfunction "2_2") (pintype "unspecified"))
      (node (ref "U12") (pin "1") (pinfunction "1_1") (pintype "unspecified"))
      (node (ref "U7") (pin "1") (pinfunction "SW_1") (pintype "unspecified"))
    )
    (net (code "51") (name "unconnected-(BUZZER1-Pad3)") (class "Default")
      (node (ref "BUZZER1") (pin "3") (pinfunction "3_3") (pintype "unspecified"))
    )
    (net (code "52") (name "unconnected-(BUZZER1-Pad4)") (class "Default")
      (node (ref "BUZZER1") (pin "4") (pinfunction "4_4") (pintype "unspecified"))
    )
    (net (code "53") (name "unconnected-(CN1-Pad5)") (class "Default")
      (node (ref "CN1") (pin "5") (pinfunction "5_5") (pintype "unspecified"))
    )
    (net (code "54") (name "unconnected-(LED2-DOUT-Pad4)") (class "Default")
      (node (ref "LED2") (pin "4") (pinfunction "DOUT_4") (pintype "unspecified"))
    )
    (net (code "55") (name "unconnected-(LED2-GND{slash}VSS-Pad1)") (class "Default")
      (node (ref "LED2") (pin "1") (pinfunction "GND/VSS_1") (pintype "unspecified"))
    )
    (net (code "56") (name "unconnected-(R11-Pad2)") (class "Default")
      (node (ref "R11") (pin "2") (pinfunction "2_2") (pintype "input"))
    )
    (net (code "57") (name "unconnected-(SW1-B-Pad2)") (class "Default")
      (node (ref "SW1") (pin "2") (pinfunction "B_2") (pintype "unspecified"))
    )
    (net (code "58") (name "unconnected-(SW1-D-Pad4)") (class "Default")
      (node (ref "SW1") (pin "4") (pinfunction "D_4") (pintype "unspecified"))
    )
    (net (code "59") (name "unconnected-(SW2-A-Pad1)") (class "Default")
      (node (ref "SW2") (pin "1") (pinfunction "A_1") (pintype "unspecified"))
    )
    (net (code "60") (name "unconnected-(SW2-D-Pad4)") (class "Default")
      (node (ref "SW2") (pin "4") (pinfunction "D_4") (pintype "unspecified"))
    )
    (net (code "61") (name "unconnected-(U1-A5-Pad24)") (class "Default")
      (node (ref "U1") (pin "24") (pinfunction "A5_24") (pintype "unspecified"))
    )
    (net (code "62") (name "unconnected-(U1-EXTCLK-Pad25)") (class "Default")
      (node (ref "U1") (pin "25") (pinfunction "EXTCLK_25") (pintype "unspecified"))
    )
    (net (code "63") (name "unconnected-(U1-LED1-Pad7)") (class "Default")
      (node (ref "U1") (pin "7") (pinfunction "LED1_7") (pintype "unspecified"))
    )
    (net (code "64") (name "unconnected-(U1-LED2-Pad8)") (class "Default")
      (node (ref "U1") (pin "8") (pinfunction "LED2_8") (pintype "unspecified"))
    )
    (net (code "65") (name "unconnected-(U1-LED3-Pad9)") (class "Default")
      (node (ref "U1") (pin "9") (pinfunction "LED3_9") (pintype "unspecified"))
    )
    (net (code "66") (name "unconnected-(U1-LED4-Pad10)") (class "Default")
      (node (ref "U1") (pin "10") (pinfunction "LED4_10") (pintype "unspecified"))
    )
    (net (code "67") (name "unconnected-(U1-LED5-Pad11)") (class "Default")
      (node (ref "U1") (pin "11") (pinfunction "LED5_11") (pintype "unspecified"))
    )
    (net (code "68") (name "unconnected-(U1-LED6-Pad12)") (class "Default")
      (node (ref "U1") (pin "12") (pinfunction "LED6_12") (pintype "unspecified"))
    )
    (net (code "69") (name "unconnected-(U1-LED7-Pad13)") (class "Default")
      (node (ref "U1") (pin "13") (pinfunction "LED7_13") (pintype "unspecified"))
    )
    (net (code "70") (name "unconnected-(U1-LED8-Pad15)") (class "Default")
      (node (ref "U1") (pin "15") (pinfunction "LED8_15") (pintype "unspecified"))
    )
    (net (code "71") (name "unconnected-(U1-LED9-Pad16)") (class "Default")
      (node (ref "U1") (pin "16") (pinfunction "LED9_16") (pintype "unspecified"))
    )
    (net (code "72") (name "unconnected-(U1-LED10-Pad17)") (class "Default")
      (node (ref "U1") (pin "17") (pinfunction "LED10_17") (pintype "unspecified"))
    )
    (net (code "73") (name "unconnected-(U1-LED11-Pad18)") (class "Default")
      (node (ref "U1") (pin "18") (pinfunction "LED11_18") (pintype "unspecified"))
    )
    (net (code "74") (name "unconnected-(U1-LED12-Pad19)") (class "Default")
      (node (ref "U1") (pin "19") (pinfunction "LED12_19") (pintype "unspecified"))
    )
    (net (code "75") (name "unconnected-(U1-LED13-Pad20)") (class "Default")
      (node (ref "U1") (pin "20") (pinfunction "LED13_20") (pintype "unspecified"))
    )
    (net (code "76") (name "unconnected-(U1-LED14-Pad21)") (class "Default")
      (node (ref "U1") (pin "21") (pinfunction "LED14_21") (pintype "unspecified"))
    )
    (net (code "77") (name "unconnected-(U1-LED15-Pad22)") (class "Default")
      (node (ref "U1") (pin "22") (pinfunction "LED15_22") (pintype "unspecified"))
    )
    (net (code "78") (name "unconnected-(U2-AIN0-Pad4)") (class "Default")
      (node (ref "U2") (pin "4") (pinfunction "AIN0_4") (pintype "unspecified"))
    )
    (net (code "79") (name "unconnected-(U2-AIN1-Pad5)") (class "Default")
      (node (ref "U2") (pin "5") (pinfunction "AIN1_5") (pintype "unspecified"))
    )
    (net (code "80") (name "unconnected-(U2-AIN2-Pad6)") (class "Default")
      (node (ref "U2") (pin "6") (pinfunction "AIN2_6") (pintype "unspecified"))
    )
    (net (code "81") (name "unconnected-(U2-AIN3-Pad7)") (class "Default")
      (node (ref "U2") (pin "7") (pinfunction "AIN3_7") (pintype "unspecified"))
    )
    (net (code "82") (name "unconnected-(U2-ALERT{slash}RDY-Pad2)") (class "Default")
      (node (ref "U2") (pin "2") (pinfunction "ALERT/RDY_2") (pintype "unspecified"))
    )
    (net (code "83") (name "unconnected-(U3-INT1{slash}INT-Pad4)") (class "Default")
      (node (ref "U3") (pin "4") (pinfunction "INT1/INT_4") (pintype "unspecified"))
    )
    (net (code "84") (name "unconnected-(U3-INT2{slash}FSYNC{slash}CLKIN-Pad9)") (class "Default")
      (node (ref "U3") (pin "9") (pinfunction "INT2/FSYNC/CLKIN_9") (pintype "unspecified"))
    )
    (net (code "85") (name "unconnected-(U3-RESV-Pad2)") (class "Default")
      (node (ref "U3") (pin "2") (pinfunction "RESV_2") (pintype "unspecified"))
    )
    (net (code "86") (name "unconnected-(U3-RESV-Pad3)") (class "Default")
      (node (ref "U3") (pin "3") (pinfunction "RESV_3") (pintype "unspecified"))
    )
    (net (code "87") (name "unconnected-(U3-RESV-Pad7)") (class "Default")
      (node (ref "U3") (pin "7") (pinfunction "RESV_7") (pintype "unspecified"))
    )
    (net (code "88") (name "unconnected-(U3-RESV-Pad10)") (class "Default")
      (node (ref "U3") (pin "10") (pinfunction "RESV_10") (pintype "unspecified"))
    )
    (net (code "89") (name "unconnected-(U3-RESV-Pad11)") (class "Default")
      (node (ref "U3") (pin "11") (pinfunction "RESV_11") (pintype "unspecified"))
    )
    (net (code "90") (name "unconnected-(U4-C1-Pad4)") (class "Default")
      (node (ref "U4") (pin "4") (pinfunction "C1_4") (pintype "unspecified"))
    )
    (net (code "91") (name "unconnected-(U4-CS-Pad10)") (class "Default")
      (node (ref "U4") (pin "10") (pinfunction "CS_10") (pintype "unspecified"))
    )
    (net (code "92") (name "unconnected-(U4-DRDY-Pad8)") (class "Default")
      (node (ref "U4") (pin "8") (pinfunction "DRDY_8") (pintype "unspecified"))
    )
    (net (code "93") (name "unconnected-(U4-INT-Pad7)") (class "Default")
      (node (ref "U4") (pin "7") (pinfunction "INT_7") (pintype "unspecified"))
    )
    (net (code "94") (name "unconnected-(U4-Res-Pad2)") (class "Default")
      (node (ref "U4") (pin "2") (pinfunction "Res_2") (pintype "unspecified"))
    )
    (net (code "95") (name "unconnected-(U4-Res-Pad12)") (class "Default")
      (node (ref "U4") (pin "12") (pinfunction "Res_12") (pintype "unspecified"))
    )
    (net (code "96") (name "unconnected-(U4-SD0{slash}SA1-Pad9)") (class "Default")
      (node (ref "U4") (pin "9") (pinfunction "SD0/SA1_9") (pintype "unspecified"))
    )
    (net (code "97") (name "unconnected-(U5-INT-Pad7)") (class "Default")
      (node (ref "U5") (pin "7") (pinfunction "INT_7") (pintype "unspecified"))
    )
    (net (code "98") (name "unconnected-(U5-SDO-Pad5)") (class "Default")
      (node (ref "U5") (pin "5") (pinfunction "SDO_5") (pintype "unspecified"))
    )
    (net (code "99") (name "unconnected-(U5-VSS-Pad9)") (class "Default")
      (node (ref "U5") (pin "9") (pinfunction "VSS_9") (pintype "unspecified"))
    )
    (net (code "100") (name "unconnected-(U6-A0-Pad2)") (class "Default")
      (node (ref "U6") (pin "2") (pinfunction "A0_2") (pintype "unspecified"))
    )
    (net (code "101") (name "unconnected-(U6-A1-Pad1)") (class "Default")
      (node (ref "U6") (pin "1") (pinfunction "A1_1") (pintype "unspecified"))
    )
    (net (code "102") (name "unconnected-(U6-Alert-Pad3)") (class "Default")
      (node (ref "U6") (pin "3") (pinfunction "Alert_3") (pintype "unspecified"))
    )
    (net (code "103") (name "unconnected-(U7-COMP-Pad3)") (class "Default")
      (node (ref "U7") (pin "3") (pinfunction "COMP_3") (pintype "unspecified"))
    )
    (net (code "104") (name "unconnected-(U7-EP-Pad9)") (class "Default")
      (node (ref "U7") (pin "9") (pinfunction "EP_9") (pintype "unspecified"))
    )
    (net (code "105") (name "unconnected-(U7-FB-Pad4)") (class "Default")
      (node (ref "U7") (pin "4") (pinfunction "FB_4") (pintype "unspecified"))
    )
    (net (code "106") (name "unconnected-(U7-FREQ-Pad6)") (class "Default")
      (node (ref "U7") (pin "6") (pinfunction "FREQ_6") (pintype "unspecified"))
    )
    (net (code "107") (name "unconnected-(U8-VOUT-Pad4)") (class "Default")
      (node (ref "U8") (pin "4") (pinfunction "VOUT_4") (pintype "unspecified"))
    )
  )
)
